# LED_Light_Control.net
KiCad netlist of a schematic drawn in EAGLE
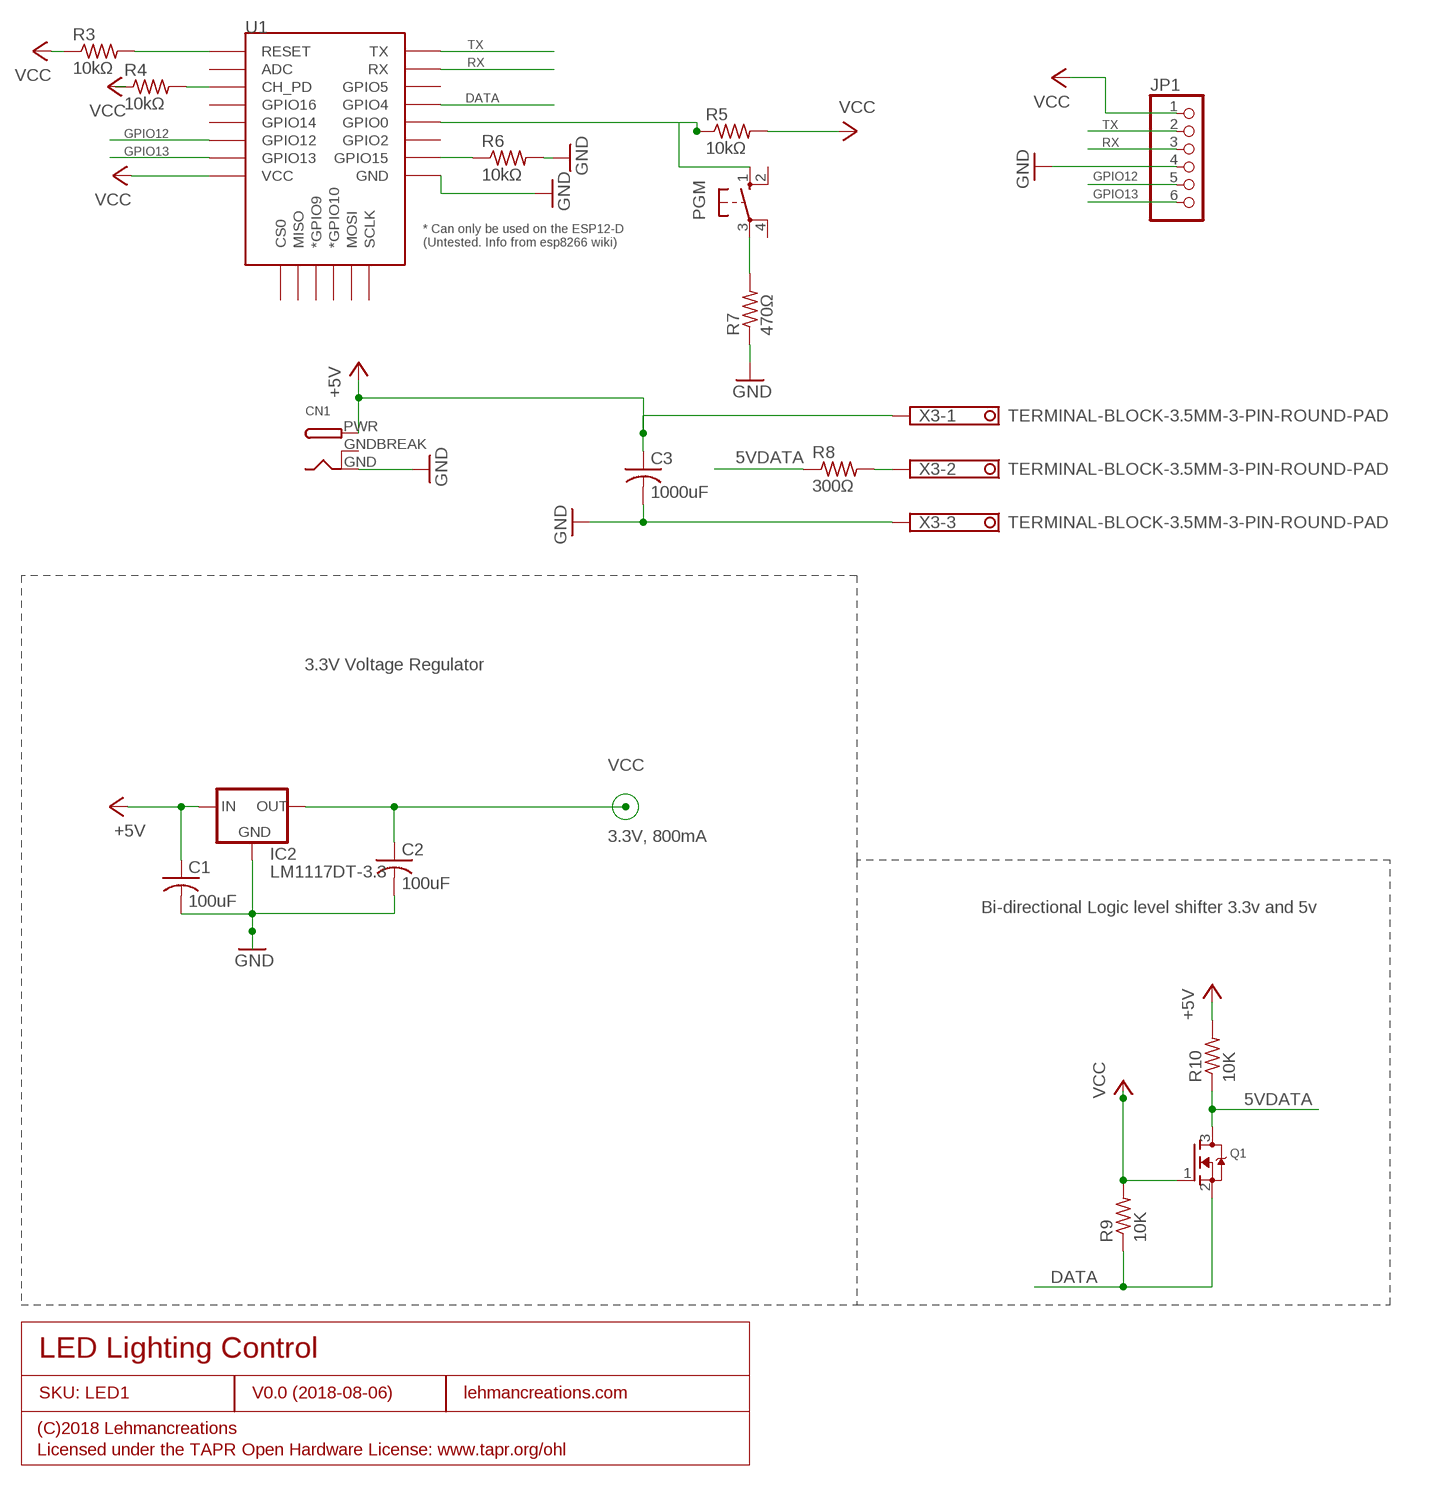
[diagram p0: schematic, sheet 1]

(export (version "E")
  (design (tool "Eeschema 10.0.6"))
  (components
    (comp (ref "C1")
      (value "100uF")
      (footprint "eagle-import:C0805")
      (libsource (lib "eagle-import") (part "C-USC0805"))
    )
    (comp (ref "C2")
      (value "100uF")
      (footprint "eagle-import:C0805")
      (libsource (lib "eagle-import") (part "C-USC0805"))
    )
    (comp (ref "C3")
      (value "1000uF")
      (footprint "eagle-import:C0805")
      (libsource (lib "eagle-import") (part "C-USC0805"))
    )
    (comp (ref "CN1")
      (value "DCBARRELPTH")
      (footprint "eagle-import:DCJACK_2MM_PTH")
      (libsource (lib "eagle-import") (part "DCBARRELPTH"))
    )
    (comp (ref "IC2")
      (value "LM1117DT-3.3")
      (footprint "eagle-import:TO252")
      (fields (field (name "MF") "Texas Instruments"))
      (libsource (lib "eagle-import") (part "LM1117?-DT3.3"))
    )
    (comp (ref "JP1")
      (value "PINHD-1X6")
      (footprint "eagle-import:1X06")
      (libsource (lib "eagle-import") (part "PINHD-1X6"))
    )
    (comp (ref "PGM")
      (value "10-XX")
      (footprint "eagle-import:B3F-10XX")
      (fields (field (name "MPN") "B3F-1000"))
      (libsource (lib "eagle-import") (part "10-XX"))
    )
    (comp (ref "Q1")
      (value "MOSFET-NWAVE")
      (footprint "eagle-import:SOT23-W")
      (libsource (lib "eagle-import") (part "MOSFET-NWAVE"))
    )
    (comp (ref "R3")
      (value "10kΩ")
      (footprint "eagle-import:R0805")
      (libsource (lib "eagle-import") (part "R-US_R0805"))
    )
    (comp (ref "R4")
      (value "10kΩ")
      (footprint "eagle-import:R0805")
      (libsource (lib "eagle-import") (part "R-US_R0805"))
    )
    (comp (ref "R5")
      (value "10kΩ")
      (footprint "eagle-import:R0805")
      (libsource (lib "eagle-import") (part "R-US_R0805"))
    )
    (comp (ref "R6")
      (value "10kΩ")
      (footprint "eagle-import:R0805")
      (libsource (lib "eagle-import") (part "R-US_R0805"))
    )
    (comp (ref "R7")
      (value "470Ω")
      (footprint "eagle-import:R0805")
      (libsource (lib "eagle-import") (part "R-US_R0805"))
    )
    (comp (ref "R8")
      (value "300Ω")
      (footprint "eagle-import:R0805")
      (libsource (lib "eagle-import") (part "R-US_R0805"))
    )
    (comp (ref "R9")
      (value "10K")
      (footprint "eagle-import:R0805")
      (libsource (lib "eagle-import") (part "R-US_R0805"))
    )
    (comp (ref "R10")
      (value "10K")
      (footprint "eagle-import:R0805")
      (libsource (lib "eagle-import") (part "R-US_R0805"))
    )
    (comp (ref "U1")
      (value "ESP12ESMD")
      (footprint "eagle-import:ESP12E-SMD")
      (libsource (lib "eagle-import") (part "ESP12ESMD"))
    )
    (comp (ref "X3")
      (value "TERMINAL-BLOCK-3.5MM-3-PIN-ROUND-PAD")
      (footprint "eagle-import:TERMINAL-BLOCK-3-PIN-3.5MM-ROUND-PAD")
      (libsource (lib "eagle-import") (part "TERMINAL-BLOCK-3.5MM-3-PIN-ROUND-PAD"))
    )
  )
  (nets
    (net (code "1") (name "+5V") (class "Default")
      (node (ref "C1") (pin "1") (pinfunction "1_1") (pintype "passive"))
      (node (ref "C3") (pin "1") (pinfunction "1_1") (pintype "passive"))
      (node (ref "CN1") (pin "PWR") (pinfunction "PWR_PWR") (pintype "power_in"))
      (node (ref "IC2") (pin "2") (pinfunction "IN_2") (pintype "input"))
      (node (ref "R10") (pin "2") (pinfunction "2_2") (pintype "passive"))
      (node (ref "X3") (pin "1") (pinfunction "K_1") (pintype "passive"))
    )
    (net (code "2") (name "/5VDATA") (class "Default")
      (node (ref "Q1") (pin "3") (pinfunction "D_3") (pintype "bidirectional"))
      (node (ref "R10") (pin "1") (pinfunction "1_1") (pintype "passive"))
      (node (ref "R8") (pin "1") (pinfunction "1_1") (pintype "passive"))
    )
    (net (code "3") (name "/DATA") (class "Default")
      (node (ref "Q1") (pin "2") (pinfunction "S_2") (pintype "bidirectional"))
      (node (ref "R9") (pin "1") (pinfunction "1_1") (pintype "passive"))
      (node (ref "U1") (pin "GPIO4") (pinfunction "GPIO4_GPIO4") (pintype "bidirectional"))
    )
    (net (code "4") (name "/GNDBREAK") (class "Default")
      (node (ref "CN1") (pin "GNDBREAK") (pinfunction "GNDBREAK_GNDBREAK") (pintype "power_in"))
    )
    (net (code "5") (name "/GPIO0") (class "Default")
      (node (ref "PGM") (pin "1") (pinfunction "S_1") (pintype "passive"))
      (node (ref "R5") (pin "1") (pinfunction "1_1") (pintype "passive"))
      (node (ref "U1") (pin "GPIO0") (pinfunction "GPIO0_GPIO0") (pintype "bidirectional"))
    )
    (net (code "6") (name "/GPIO12") (class "Default")
      (node (ref "JP1") (pin "5") (pinfunction "5_5") (pintype "passive"))
      (node (ref "U1") (pin "GPIO12") (pinfunction "GPIO12_GPIO12") (pintype "bidirectional"))
    )
    (net (code "7") (name "/GPIO13") (class "Default")
      (node (ref "JP1") (pin "6") (pinfunction "6_6") (pintype "passive"))
      (node (ref "U1") (pin "GPIO13") (pinfunction "GPIO13_GPIO13") (pintype "bidirectional"))
    )
    (net (code "8") (name "/RX") (class "Default")
      (node (ref "JP1") (pin "3") (pinfunction "3_3") (pintype "passive"))
      (node (ref "U1") (pin "RXD0") (pinfunction "RX_RXD0") (pintype "bidirectional"))
    )
    (net (code "9") (name "/TX") (class "Default")
      (node (ref "JP1") (pin "2") (pinfunction "2_2") (pintype "passive"))
      (node (ref "U1") (pin "TXD0") (pinfunction "TX_TXD0") (pintype "bidirectional"))
    )
    (net (code "10") (name "GND") (class "Default")
      (node (ref "C1") (pin "2") (pinfunction "2_2") (pintype "passive"))
      (node (ref "C2") (pin "2") (pinfunction "2_2") (pintype "passive"))
      (node (ref "C3") (pin "2") (pinfunction "2_2") (pintype "passive"))
      (node (ref "CN1") (pin "GND") (pinfunction "GND_GND") (pintype "power_in"))
      (node (ref "IC2") (pin "1") (pinfunction "GND_1") (pintype "input"))
      (node (ref "JP1") (pin "4") (pinfunction "4_4") (pintype "passive"))
      (node (ref "R6") (pin "2") (pinfunction "2_2") (pintype "passive"))
      (node (ref "R7") (pin "1") (pinfunction "1_1") (pintype "passive"))
      (node (ref "U1") (pin "GND") (pinfunction "GND_GND") (pintype "bidirectional"))
      (node (ref "X3") (pin "3") (pinfunction "K_3") (pintype "passive"))
    )
    (net (code "11") (name "Net-(PGM-P)") (class "Default")
      (node (ref "PGM") (pin "3") (pinfunction "P_3") (pintype "passive"))
      (node (ref "R7") (pin "2") (pinfunction "2_2") (pintype "passive"))
    )
    (net (code "12") (name "Net-(R3-Pad2)") (class "Default")
      (node (ref "R3") (pin "2") (pinfunction "2_2") (pintype "passive"))
      (node (ref "U1") (pin "RESET") (pinfunction "RESET_RESET") (pintype "bidirectional"))
    )
    (net (code "13") (name "Net-(R4-Pad2)") (class "Default")
      (node (ref "R4") (pin "2") (pinfunction "2_2") (pintype "passive"))
      (node (ref "U1") (pin "CH_PD") (pinfunction "CH_PD_CH_PD") (pintype "bidirectional"))
    )
    (net (code "14") (name "Net-(R6-Pad1)") (class "Default")
      (node (ref "R6") (pin "1") (pinfunction "1_1") (pintype "passive"))
      (node (ref "U1") (pin "GPIO15") (pinfunction "GPIO15_GPIO15") (pintype "bidirectional"))
    )
    (net (code "15") (name "Net-(X3B-K)") (class "Default")
      (node (ref "R8") (pin "2") (pinfunction "2_2") (pintype "passive"))
      (node (ref "X3") (pin "2") (pinfunction "K_2") (pintype "passive"))
    )
    (net (code "16") (name "VCC") (class "Default")
      (node (ref "C2") (pin "1") (pinfunction "1_1") (pintype "passive"))
      (node (ref "IC2") (pin "3") (pinfunction "OUT_3") (pintype "passive"))
      (node (ref "JP1") (pin "1") (pinfunction "1_1") (pintype "passive"))
      (node (ref "Q1") (pin "1") (pinfunction "G_1") (pintype "bidirectional"))
      (node (ref "R3") (pin "1") (pinfunction "1_1") (pintype "passive"))
      (node (ref "R4") (pin "1") (pinfunction "1_1") (pintype "passive"))
      (node (ref "R5") (pin "2") (pinfunction "2_2") (pintype "passive"))
      (node (ref "R9") (pin "2") (pinfunction "2_2") (pintype "passive"))
      (node (ref "U1") (pin "VCC") (pinfunction "VCC_VCC") (pintype "bidirectional"))
    )
    (net (code "17") (name "unconnected-(PGM-P1-Pad4)") (class "Default")
      (node (ref "PGM") (pin "4") (pinfunction "P1_4") (pintype "passive"))
    )
    (net (code "18") (name "unconnected-(PGM-S1-Pad2)") (class "Default")
      (node (ref "PGM") (pin "2") (pinfunction "S1_2") (pintype "passive"))
    )
    (net (code "19") (name "unconnected-(U1-*GPIO9-PadGPIO9)") (class "Default")
      (node (ref "U1") (pin "GPIO9") (pinfunction "*GPIO9_GPIO9") (pintype "bidirectional"))
    )
    (net (code "20") (name "unconnected-(U1-*GPIO10-PadGPIO10)") (class "Default")
      (node (ref "U1") (pin "GPIO10") (pinfunction "*GPIO10_GPIO10") (pintype "bidirectional"))
    )
    (net (code "21") (name "unconnected-(U1-PadADC)") (class "Default")
      (node (ref "U1") (pin "ADC") (pinfunction "ADC_ADC") (pintype "bidirectional"))
    )
    (net (code "22") (name "unconnected-(U1-PadCS0)") (class "Default")
      (node (ref "U1") (pin "CS0") (pinfunction "CS0_CS0") (pintype "bidirectional"))
    )
    (net (code "23") (name "unconnected-(U1-PadGPIO2)") (class "Default")
      (node (ref "U1") (pin "GPIO2") (pinfunction "GPIO2_GPIO2") (pintype "bidirectional"))
    )
    (net (code "24") (name "unconnected-(U1-PadGPIO5)") (class "Default")
      (node (ref "U1") (pin "GPIO5") (pinfunction "GPIO5_GPIO5") (pintype "bidirectional"))
    )
    (net (code "25") (name "unconnected-(U1-PadGPIO14)") (class "Default")
      (node (ref "U1") (pin "GPIO14") (pinfunction "GPIO14_GPIO14") (pintype "bidirectional"))
    )
    (net (code "26") (name "unconnected-(U1-PadGPIO16)") (class "Default")
      (node (ref "U1") (pin "GPIO16") (pinfunction "GPIO16_GPIO16") (pintype "bidirectional"))
    )
    (net (code "27") (name "unconnected-(U1-PadMISO)") (class "Default")
      (node (ref "U1") (pin "MISO") (pinfunction "MISO_MISO") (pintype "bidirectional"))
    )
    (net (code "28") (name "unconnected-(U1-PadMOSI)") (class "Default")
      (node (ref "U1") (pin "MOSI") (pinfunction "MOSI_MOSI") (pintype "bidirectional"))
    )
    (net (code "29") (name "unconnected-(U1-PadSCLK)") (class "Default")
      (node (ref "U1") (pin "SCLK") (pinfunction "SCLK_SCLK") (pintype "bidirectional"))
    )
  )
)
